# WIZ500SR_RP_EVB.net
KiCad netlist of a schematic drawn in Altium Designer
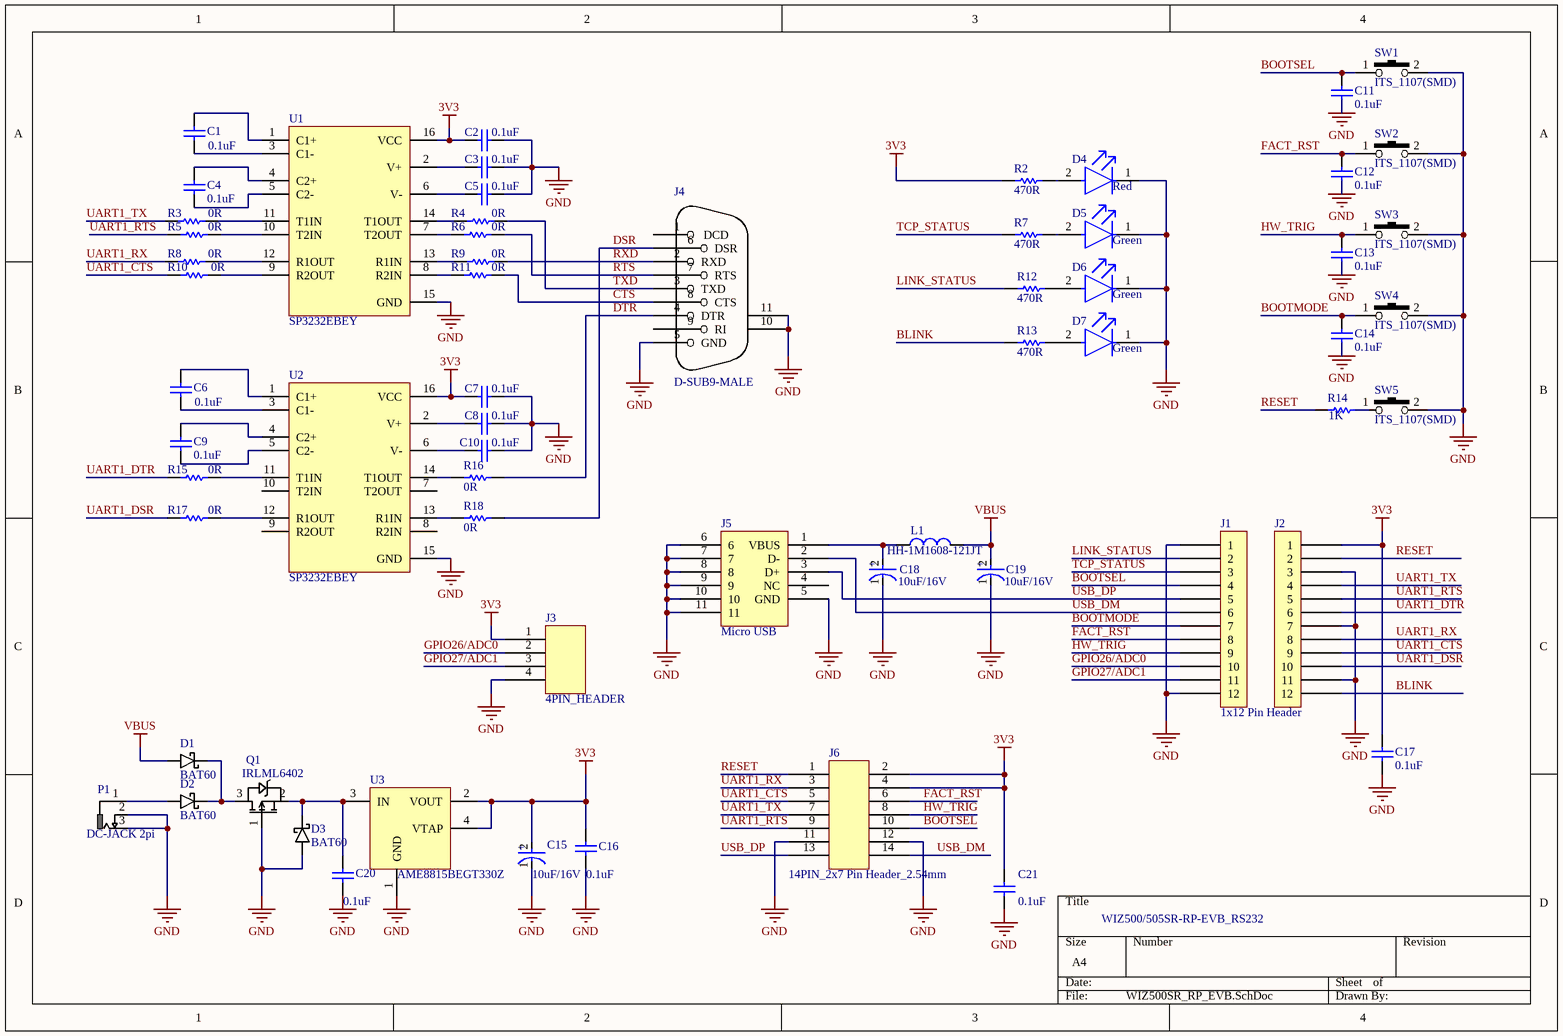
[diagram p0: WIZ500SR_RP_EVB.SchDoc]

(export (version "E")
  (design (tool "Eeschema 10.0.6"))
  (components
    (comp (ref "C1")
      (value "0.1uF")
      (footprint "CAPC1005X55X25ML5T10")
      (description "Chip Capacitor, 1 nF, +/- 10%, 50 V, -55 to 125 degC, 0402 (1005 Metric), RoHS, Tape and Reel")
      (fields (field (name "TOLERANCE") "10%"))
      (libsource (lib "Altium Content Vault") (part "CAP-NP-2"))
    )
    (comp (ref "C2")
      (value "0.1uF")
      (footprint "CAPC1005X55X25ML5T10")
      (description "Chip Capacitor, 1 nF, +/- 10%, 50 V, -55 to 125 degC, 0402 (1005 Metric), RoHS, Tape and Reel")
      (fields (field (name "TOLERANCE") "10%"))
      (libsource (lib "Altium Content Vault") (part "CAP-NP-2"))
    )
    (comp (ref "C3")
      (value "0.1uF")
      (footprint "CAPC1005X55X25ML5T10")
      (description "Chip Capacitor, 1 nF, +/- 10%, 50 V, -55 to 125 degC, 0402 (1005 Metric), RoHS, Tape and Reel")
      (fields (field (name "TOLERANCE") "10%"))
      (libsource (lib "Altium Content Vault") (part "CAP-NP-2"))
    )
    (comp (ref "C4")
      (value "0.1uF")
      (footprint "CAPC1005X55X25ML5T10")
      (description "Chip Capacitor, 1 nF, +/- 10%, 50 V, -55 to 125 degC, 0402 (1005 Metric), RoHS, Tape and Reel")
      (fields (field (name "TOLERANCE") "10%"))
      (libsource (lib "Altium Content Vault") (part "CAP-NP-2"))
    )
    (comp (ref "C5")
      (value "0.1uF")
      (footprint "CAPC1005X55X25ML5T10")
      (description "Chip Capacitor, 1 nF, +/- 10%, 50 V, -55 to 125 degC, 0402 (1005 Metric), RoHS, Tape and Reel")
      (fields (field (name "TOLERANCE") "10%"))
      (libsource (lib "Altium Content Vault") (part "CAP-NP-2"))
    )
    (comp (ref "C6")
      (value "0.1uF")
      (footprint "CAPC1005X55X25ML5T10")
      (description "Chip Capacitor, 1 nF, +/- 10%, 50 V, -55 to 125 degC, 0402 (1005 Metric), RoHS, Tape and Reel")
      (fields (field (name "TOLERANCE") "10%"))
      (libsource (lib "Altium Content Vault") (part "CAP-NP-2"))
    )
    (comp (ref "C7")
      (value "0.1uF")
      (footprint "CAPC1005X55X25ML5T10")
      (description "Chip Capacitor, 1 nF, +/- 10%, 50 V, -55 to 125 degC, 0402 (1005 Metric), RoHS, Tape and Reel")
      (fields (field (name "TOLERANCE") "10%"))
      (libsource (lib "Altium Content Vault") (part "CAP-NP-2"))
    )
    (comp (ref "C8")
      (value "0.1uF")
      (footprint "CAPC1005X55X25ML5T10")
      (description "Chip Capacitor, 1 nF, +/- 10%, 50 V, -55 to 125 degC, 0402 (1005 Metric), RoHS, Tape and Reel")
      (fields (field (name "TOLERANCE") "10%"))
      (libsource (lib "Altium Content Vault") (part "CAP-NP-2"))
    )
    (comp (ref "C9")
      (value "0.1uF")
      (footprint "CAPC1005X55X25ML5T10")
      (description "Chip Capacitor, 1 nF, +/- 10%, 50 V, -55 to 125 degC, 0402 (1005 Metric), RoHS, Tape and Reel")
      (fields (field (name "TOLERANCE") "10%"))
      (libsource (lib "Altium Content Vault") (part "CAP-NP-2"))
    )
    (comp (ref "C10")
      (value "0.1uF")
      (footprint "CAPC1005X55X25ML5T10")
      (description "Chip Capacitor, 1 nF, +/- 10%, 50 V, -55 to 125 degC, 0402 (1005 Metric), RoHS, Tape and Reel")
      (fields (field (name "TOLERANCE") "10%"))
      (libsource (lib "Altium Content Vault") (part "CAP-NP-2"))
    )
    (comp (ref "C11")
      (value "0.1uF")
      (footprint "CAPC1005X55X25ML5T10")
      (description "Chip Capacitor, 1 nF, +/- 10%, 50 V, -55 to 125 degC, 0402 (1005 Metric), RoHS, Tape and Reel")
      (fields (field (name "TOLERANCE") "10%"))
      (libsource (lib "Altium Content Vault") (part "CAP-NP-2"))
    )
    (comp (ref "C12")
      (value "0.1uF")
      (footprint "CAPC1005X55X25ML5T10")
      (description "Chip Capacitor, 1 nF, +/- 10%, 50 V, -55 to 125 degC, 0402 (1005 Metric), RoHS, Tape and Reel")
      (fields (field (name "TOLERANCE") "10%"))
      (libsource (lib "Altium Content Vault") (part "CAP-NP-2"))
    )
    (comp (ref "C13")
      (value "0.1uF")
      (footprint "CAPC1005X55X25ML5T10")
      (description "Chip Capacitor, 1 nF, +/- 10%, 50 V, -55 to 125 degC, 0402 (1005 Metric), RoHS, Tape and Reel")
      (fields (field (name "TOLERANCE") "10%"))
      (libsource (lib "Altium Content Vault") (part "CAP-NP-2"))
    )
    (comp (ref "C14")
      (value "0.1uF")
      (footprint "CAPC1005X55X25ML5T10")
      (description "Chip Capacitor, 1 nF, +/- 10%, 50 V, -55 to 125 degC, 0402 (1005 Metric), RoHS, Tape and Reel")
      (fields (field (name "TOLERANCE") "10%"))
      (libsource (lib "Altium Content Vault") (part "CAP-NP-2"))
    )
    (comp (ref "C15")
      (value "10uF/16V")
      (footprint "FP-T520A107M006ATE045-MFG")
      (description "CAP TANT POLY 100UF 6.3V 1206")
      (fields (field (name "TOLERANCE") "20%"))
      (libsource (lib "Altium Content Vault") (part "a00bbbee19879c290e62620ae7e47b1"))
    )
    (comp (ref "C16")
      (value "0.1uF")
      (footprint "CAPC1005X55X25ML5T10")
      (description "Chip Capacitor, 1 nF, +/- 10%, 50 V, -55 to 125 degC, 0402 (1005 Metric), RoHS, Tape and Reel")
      (fields (field (name "TOLERANCE") "10%"))
      (libsource (lib "Altium Content Vault") (part "CAP-NP-2"))
    )
    (comp (ref "C17")
      (value "0.1uF")
      (footprint "CAPC1005X55X25ML5T10")
      (description "Chip Capacitor, 1 nF, +/- 10%, 50 V, -55 to 125 degC, 0402 (1005 Metric), RoHS, Tape and Reel")
      (fields (field (name "TOLERANCE") "10%"))
      (libsource (lib "Altium Content Vault") (part "CAP-NP-2"))
    )
    (comp (ref "C18")
      (value "10uF/16V")
      (footprint "FP-T520A107M006ATE045-MFG")
      (description "CAP TANT POLY 100UF 6.3V 1206")
      (fields (field (name "TOLERANCE") "20%"))
      (libsource (lib "Altium Content Vault") (part "a00bbbee19879c290e62620ae7e47b1"))
    )
    (comp (ref "C19")
      (value "10uF/16V")
      (footprint "FP-T520A107M006ATE045-MFG")
      (description "CAP TANT POLY 100UF 6.3V 1206")
      (fields (field (name "TOLERANCE") "20%"))
      (libsource (lib "Altium Content Vault") (part "a00bbbee19879c290e62620ae7e47b1"))
    )
    (comp (ref "C20")
      (value "0.1uF")
      (footprint "CAPC1005X55X25ML5T10")
      (description "Chip Capacitor, 1 nF, +/- 10%, 50 V, -55 to 125 degC, 0402 (1005 Metric), RoHS, Tape and Reel")
      (fields (field (name "TOLERANCE") "10%"))
      (libsource (lib "Altium Content Vault") (part "CAP-NP-2"))
    )
    (comp (ref "C21")
      (value "0.1uF")
      (footprint "CAPC1005X55X25ML5T10")
      (description "Chip Capacitor, 1 nF, +/- 10%, 50 V, -55 to 125 degC, 0402 (1005 Metric), RoHS, Tape and Reel")
      (fields (field (name "TOLERANCE") "10%"))
      (libsource (lib "Altium Content Vault") (part "CAP-NP-2"))
    )
    (comp (ref "D1")
      (value "BAT60")
      (footprint "BAT60A")
      (libsource (lib "Integrated_Library1") (part "Schottky_Diode(BAT60)"))
    )
    (comp (ref "D2")
      (value "BAT60")
      (footprint "BAT60A")
      (libsource (lib "Integrated_Library1") (part "Schottky_Diode(BAT60)"))
    )
    (comp (ref "D3")
      (value "BAT60")
      (footprint "BAT60A")
      (libsource (lib "Integrated_Library1") (part "Schottky_Diode(BAT60)"))
    )
    (comp (ref "D4")
      (value "Red")
      (footprint "FP-LTST-C191TBKT-MFG")
      (description "LED BLUE CLEAR CHIP SMD")
      (libsource (lib "Altium Content Vault") (part "8706943c75ba83719d021d2fdc84c58"))
    )
    (comp (ref "D5")
      (value "Green")
      (footprint "FP-LTST-C191TBKT-MFG")
      (description "LED BLUE CLEAR CHIP SMD")
      (libsource (lib "Altium Content Vault") (part "8706943c75ba83719d021d2fdc84c58"))
    )
    (comp (ref "D6")
      (value "Green")
      (footprint "FP-LTST-C191TBKT-MFG")
      (description "LED BLUE CLEAR CHIP SMD")
      (libsource (lib "Altium Content Vault") (part "8706943c75ba83719d021d2fdc84c58"))
    )
    (comp (ref "D7")
      (value "Green")
      (footprint "FP-LTST-C191TBKT-MFG")
      (description "LED BLUE CLEAR CHIP SMD")
      (libsource (lib "Altium Content Vault") (part "8706943c75ba83719d021d2fdc84c58"))
    )
    (comp (ref "J1")
      (value "1x12 Pin Header")
      (footprint "12PIN_HEADER_2mm")
      (libsource (lib "Integrated_Library1") (part "12PIN_2mm"))
    )
    (comp (ref "J2")
      (value "1x12 Pin Header")
      (footprint "12PIN_HEADER_2mm")
      (libsource (lib "") (part "12PIN_2mm_1"))
    )
    (comp (ref "J3")
      (value "4PIN_HEADER")
      (footprint "4PIN_HEADER")
      (libsource (lib "Integrated_Library1") (part "4PIN"))
    )
    (comp (ref "J4")
      (value "D-SUB9-MALE")
      (footprint "D-SUB9-MALE")
      (libsource (lib "Integrated_Library1") (part "D-SUB9-MALE"))
    )
    (comp (ref "J5")
      (value "Micro USB")
      (footprint "USB-MICRO-B(SMD)")
      (libsource (lib "Integrated_Library1") (part "Micro USB 5Pin"))
    )
    (comp (ref "J6")
      (value "14PIN_2x7 Pin Header_2.54mm")
      (footprint "14PIN_HEADER_2x7")
      (libsource (lib "Integrated_Library1") (part "14PIN_2x7 Pin Header_2.54mm"))
    )
    (comp (ref "L1")
      (value "HH-1M1608-121JT")
      (footprint "HH-1M11608-121JT")
      (libsource (lib "Integrated_Library1") (part "HH-1M1608-121JT"))
    )
    (comp (ref "P1")
      (value "DC-JACK 2pi")
      (footprint "DC-JACK 2PI")
      (libsource (lib "Integrated_Library1") (part "DC-JACK 2pi"))
    )
    (comp (ref "Q1")
      (value "IRLML6402")
      (footprint "IRLML6402")
      (libsource (lib "Integrated_Library1") (part "IRLML6402"))
    )
    (comp (ref "R2")
      (value "470R")
      (footprint "RESC1005X40X25NL05T10")
      (fields (field (name "MANUFACTURER") "Yageo / Phycomp") (field (name "PART NUMBER") "RC0402JR-070RL"))
      (libsource (lib "Altium Content Vault") (part "RES"))
    )
    (comp (ref "R3")
      (value "0R")
      (footprint "RESC1005X40X25NL05T10")
      (fields (field (name "MANUFACTURER") "Yageo / Phycomp") (field (name "PART NUMBER") "RC0402JR-070RL"))
      (libsource (lib "Altium Content Vault") (part "RES"))
    )
    (comp (ref "R4")
      (value "0R")
      (footprint "RESC1005X40X25NL05T10")
      (fields (field (name "MANUFACTURER") "Yageo / Phycomp") (field (name "PART NUMBER") "RC0402JR-070RL"))
      (libsource (lib "Altium Content Vault") (part "RES"))
    )
    (comp (ref "R5")
      (value "0R")
      (footprint "RESC1005X40X25NL05T10")
      (fields (field (name "MANUFACTURER") "Yageo / Phycomp") (field (name "PART NUMBER") "RC0402JR-070RL"))
      (libsource (lib "Altium Content Vault") (part "RES"))
    )
    (comp (ref "R6")
      (value "0R")
      (footprint "RESC1005X40X25NL05T10")
      (fields (field (name "MANUFACTURER") "Yageo / Phycomp") (field (name "PART NUMBER") "RC0402JR-070RL"))
      (libsource (lib "Altium Content Vault") (part "RES"))
    )
    (comp (ref "R7")
      (value "470R")
      (footprint "RESC1005X40X25NL05T10")
      (fields (field (name "MANUFACTURER") "Yageo / Phycomp") (field (name "PART NUMBER") "RC0402JR-070RL"))
      (libsource (lib "Altium Content Vault") (part "RES"))
    )
    (comp (ref "R8")
      (value "0R")
      (footprint "RESC1005X40X25NL05T10")
      (fields (field (name "MANUFACTURER") "Yageo / Phycomp") (field (name "PART NUMBER") "RC0402JR-070RL"))
      (libsource (lib "Altium Content Vault") (part "RES"))
    )
    (comp (ref "R9")
      (value "0R")
      (footprint "RESC1005X40X25NL05T10")
      (fields (field (name "MANUFACTURER") "Yageo / Phycomp") (field (name "PART NUMBER") "RC0402JR-070RL"))
      (libsource (lib "Altium Content Vault") (part "RES"))
    )
    (comp (ref "R10")
      (value "0R")
      (footprint "RESC1005X40X25NL05T10")
      (fields (field (name "MANUFACTURER") "Yageo / Phycomp") (field (name "PART NUMBER") "RC0402JR-070RL"))
      (libsource (lib "Altium Content Vault") (part "RES"))
    )
    (comp (ref "R11")
      (value "0R")
      (footprint "RESC1005X40X25NL05T10")
      (fields (field (name "MANUFACTURER") "Yageo / Phycomp") (field (name "PART NUMBER") "RC0402JR-070RL"))
      (libsource (lib "Altium Content Vault") (part "RES"))
    )
    (comp (ref "R12")
      (value "470R")
      (footprint "RESC1005X40X25NL05T10")
      (fields (field (name "MANUFACTURER") "Yageo / Phycomp") (field (name "PART NUMBER") "RC0402JR-070RL"))
      (libsource (lib "Altium Content Vault") (part "RES"))
    )
    (comp (ref "R13")
      (value "470R")
      (footprint "RESC1005X40X25NL05T10")
      (fields (field (name "MANUFACTURER") "Yageo / Phycomp") (field (name "PART NUMBER") "RC0402JR-070RL"))
      (libsource (lib "Altium Content Vault") (part "RES"))
    )
    (comp (ref "R14")
      (value "1K")
      (footprint "RESC1005X40X25NL05T10")
      (fields (field (name "MANUFACTURER") "Yageo / Phycomp") (field (name "PART NUMBER") "RC0402JR-070RL"))
      (libsource (lib "Altium Content Vault") (part "RES"))
    )
    (comp (ref "R15")
      (value "0R")
      (footprint "RESC1005X40X25NL05T10")
      (fields (field (name "MANUFACTURER") "Yageo / Phycomp") (field (name "PART NUMBER") "RC0402JR-070RL"))
      (libsource (lib "Altium Content Vault") (part "RES"))
    )
    (comp (ref "R16")
      (value "0R")
      (footprint "RESC1005X40X25NL05T10")
      (fields (field (name "MANUFACTURER") "Yageo / Phycomp") (field (name "PART NUMBER") "RC0402JR-070RL"))
      (libsource (lib "Altium Content Vault") (part "RES"))
    )
    (comp (ref "R17")
      (value "0R")
      (footprint "RESC1005X40X25NL05T10")
      (fields (field (name "MANUFACTURER") "Yageo / Phycomp") (field (name "PART NUMBER") "RC0402JR-070RL"))
      (libsource (lib "Altium Content Vault") (part "RES"))
    )
    (comp (ref "R18")
      (value "0R")
      (footprint "RESC1005X40X25NL05T10")
      (fields (field (name "MANUFACTURER") "Yageo / Phycomp") (field (name "PART NUMBER") "RC0402JR-070RL"))
      (libsource (lib "Altium Content Vault") (part "RES"))
    )
    (comp (ref "SW1")
      (value "ITS_1107(SMD)")
      (footprint "IT-1107(SMD)")
      (libsource (lib "Integrated_Library1") (part "ITS_1107(SW)"))
    )
    (comp (ref "SW2")
      (value "ITS_1107(SMD)")
      (footprint "IT-1107(SMD)")
      (libsource (lib "Integrated_Library1") (part "ITS_1107(SW)"))
    )
    (comp (ref "SW3")
      (value "ITS_1107(SMD)")
      (footprint "IT-1107(SMD)")
      (libsource (lib "Integrated_Library1") (part "ITS_1107(SW)"))
    )
    (comp (ref "SW4")
      (value "ITS_1107(SMD)")
      (footprint "IT-1107(SMD)")
      (libsource (lib "Integrated_Library1") (part "ITS_1107(SW)"))
    )
    (comp (ref "SW5")
      (value "ITS_1107(SMD)")
      (footprint "IT-1107(SMD)")
      (libsource (lib "Integrated_Library1") (part "ITS_1107(SW)"))
    )
    (comp (ref "U1")
      (value "SP3232EBEY")
      (footprint "SP3232EBEY-TSSOP16")
      (libsource (lib "Integrated_Library1") (part "SP3232EBEY"))
    )
    (comp (ref "U2")
      (value "SP3232EBEY")
      (footprint "SP3232EBEY-TSSOP16")
      (libsource (lib "Integrated_Library1") (part "SP3232EBEY"))
    )
    (comp (ref "U3")
      (value "AME8815BEGT330Z")
      (footprint "AME8815BEGT330Z")
      (libsource (lib "Integrated_Library1") (part "AME8815BEGT330Z(3.3_LDO)"))
    )
  )
  (nets
    (net (code "2") (name "/BLINK") (class "Default")
      (node (ref "J2") (pin "12") (pinfunction "12_12") (pintype "passive"))
      (node (ref "R13") (pin "1") (pinfunction "1_1") (pintype "passive"))
    )
    (net (code "3") (name "/BOOTMODE") (class "Default")
      (node (ref "C14") (pin "2") (pinfunction "2_2") (pintype "passive"))
      (node (ref "J1") (pin "7") (pinfunction "7_7") (pintype "passive"))
      (node (ref "SW4") (pin "1") (pinfunction "1_1") (pintype "passive"))
    )
    (net (code "4") (name "/BOOTSEL") (class "Default")
      (node (ref "C11") (pin "2") (pinfunction "2_2") (pintype "passive"))
      (node (ref "J1") (pin "4") (pinfunction "4_4") (pintype "passive"))
      (node (ref "J6") (pin "10") (pintype "passive"))
      (node (ref "SW1") (pin "1") (pinfunction "1_1") (pintype "passive"))
    )
    (net (code "5") (name "/CTS") (class "Default")
      (node (ref "J4") (pin "8") (pinfunction "CTS_8") (pintype "passive"))
      (node (ref "R11") (pin "2") (pinfunction "2_2") (pintype "passive"))
    )
    (net (code "6") (name "/DSR") (class "Default")
      (node (ref "J4") (pin "6") (pinfunction "DSR_6") (pintype "passive"))
      (node (ref "R18") (pin "2") (pinfunction "2_2") (pintype "passive"))
    )
    (net (code "7") (name "/DTR") (class "Default")
      (node (ref "J4") (pin "4") (pinfunction "DTR_4") (pintype "passive"))
      (node (ref "R16") (pin "2") (pinfunction "2_2") (pintype "passive"))
    )
    (net (code "8") (name "/FACT_RST") (class "Default")
      (node (ref "C12") (pin "2") (pinfunction "2_2") (pintype "passive"))
      (node (ref "J1") (pin "8") (pinfunction "8_8") (pintype "passive"))
      (node (ref "J6") (pin "6") (pintype "passive"))
      (node (ref "SW2") (pin "1") (pinfunction "1_1") (pintype "passive"))
    )
    (net (code "9") (name "/GPIO26{slash}ADC0") (class "Default")
      (node (ref "J1") (pin "10") (pinfunction "10_10") (pintype "passive"))
      (node (ref "J3") (pin "2") (pintype "passive"))
    )
    (net (code "10") (name "/GPIO27{slash}ADC1") (class "Default")
      (node (ref "J1") (pin "11") (pinfunction "11_11") (pintype "passive"))
      (node (ref "J3") (pin "3") (pintype "passive"))
    )
    (net (code "11") (name "/HW_TRIG") (class "Default")
      (node (ref "C13") (pin "2") (pinfunction "2_2") (pintype "passive"))
      (node (ref "J1") (pin "9") (pinfunction "9_9") (pintype "passive"))
      (node (ref "J6") (pin "8") (pintype "passive"))
      (node (ref "SW3") (pin "1") (pinfunction "1_1") (pintype "passive"))
    )
    (net (code "12") (name "/LINK_STATUS") (class "Default")
      (node (ref "J1") (pin "2") (pinfunction "2_2") (pintype "passive"))
      (node (ref "R12") (pin "1") (pinfunction "1_1") (pintype "passive"))
    )
    (net (code "13") (name "/RESET") (class "Default")
      (node (ref "J2") (pin "2") (pinfunction "2_2") (pintype "passive"))
      (node (ref "J6") (pin "1") (pintype "passive"))
      (node (ref "R14") (pin "1") (pinfunction "1_1") (pintype "passive"))
    )
    (net (code "14") (name "/RTS") (class "Default")
      (node (ref "J4") (pin "7") (pinfunction "RTS_7") (pintype "passive"))
      (node (ref "R6") (pin "2") (pinfunction "2_2") (pintype "passive"))
    )
    (net (code "15") (name "/RXD") (class "Default")
      (node (ref "J4") (pin "2") (pinfunction "RXD_2") (pintype "passive"))
      (node (ref "R9") (pin "2") (pinfunction "2_2") (pintype "passive"))
    )
    (net (code "16") (name "/TCP_STATUS") (class "Default")
      (node (ref "J1") (pin "3") (pinfunction "3_3") (pintype "passive"))
      (node (ref "R7") (pin "1") (pinfunction "1_1") (pintype "passive"))
    )
    (net (code "17") (name "/TXD") (class "Default")
      (node (ref "J4") (pin "3") (pinfunction "TXD_3") (pintype "passive"))
      (node (ref "R4") (pin "2") (pinfunction "2_2") (pintype "passive"))
    )
    (net (code "18") (name "/UART1_CTS") (class "Default")
      (node (ref "J2") (pin "9") (pinfunction "9_9") (pintype "passive"))
      (node (ref "J6") (pin "5") (pintype "passive"))
      (node (ref "R10") (pin "1") (pinfunction "1_1") (pintype "passive"))
    )
    (net (code "19") (name "/UART1_DSR") (class "Default")
      (node (ref "J2") (pin "10") (pinfunction "10_10") (pintype "passive"))
      (node (ref "R17") (pin "1") (pinfunction "1_1") (pintype "passive"))
    )
    (net (code "20") (name "/UART1_DTR") (class "Default")
      (node (ref "J2") (pin "6") (pinfunction "6_6") (pintype "passive"))
      (node (ref "R15") (pin "1") (pinfunction "1_1") (pintype "passive"))
    )
    (net (code "21") (name "/UART1_RTS") (class "Default")
      (node (ref "J2") (pin "5") (pinfunction "5_5") (pintype "passive"))
      (node (ref "J6") (pin "9") (pintype "passive"))
      (node (ref "R5") (pin "1") (pinfunction "1_1") (pintype "passive"))
    )
    (net (code "22") (name "/UART1_RX") (class "Default")
      (node (ref "J2") (pin "8") (pinfunction "8_8") (pintype "passive"))
      (node (ref "J6") (pin "3") (pintype "passive"))
      (node (ref "R8") (pin "1") (pinfunction "1_1") (pintype "passive"))
    )
    (net (code "23") (name "/UART1_TX") (class "Default")
      (node (ref "J2") (pin "4") (pinfunction "4_4") (pintype "passive"))
      (node (ref "J6") (pin "7") (pintype "passive"))
      (node (ref "R3") (pin "1") (pinfunction "1_1") (pintype "passive"))
    )
    (net (code "24") (name "/USB_DM") (class "Default")
      (node (ref "J1") (pin "6") (pinfunction "6_6") (pintype "passive"))
      (node (ref "J5") (pin "2") (pinfunction "D-_2") (pintype "passive"))
      (node (ref "J6") (pin "14") (pintype "passive"))
    )
    (net (code "25") (name "/USB_DP") (class "Default")
      (node (ref "J1") (pin "5") (pinfunction "5_5") (pintype "passive"))
      (node (ref "J5") (pin "3") (pinfunction "D+_3") (pintype "passive"))
      (node (ref "J6") (pin "13") (pintype "passive"))
    )
    (net (code "26") (name "3V3") (class "Default")
      (node (ref "C15") (pin "2") (pinfunction "A_2") (pintype "passive"))
      (node (ref "C16") (pin "2") (pinfunction "2_2") (pintype "passive"))
      (node (ref "C17") (pin "2") (pinfunction "2_2") (pintype "passive"))
      (node (ref "C2") (pin "1") (pinfunction "1_1") (pintype "passive"))
      (node (ref "C21") (pin "2") (pinfunction "2_2") (pintype "passive"))
      (node (ref "C7") (pin "1") (pinfunction "1_1") (pintype "passive"))
      (node (ref "J2") (pin "1") (pinfunction "1_1") (pintype "passive"))
      (node (ref "J3") (pin "1") (pintype "passive"))
      (node (ref "J6") (pin "2") (pintype "passive"))
      (node (ref "J6") (pin "4") (pintype "passive"))
      (node (ref "R2") (pin "1") (pinfunction "1_1") (pintype "passive"))
      (node (ref "U1") (pin "16") (pinfunction "VCC_16") (pintype "passive"))
      (node (ref "U2") (pin "16") (pinfunction "VCC_16") (pintype "passive"))
      (node (ref "U3") (pin "2") (pinfunction "VOUT_2") (pintype "passive"))
      (node (ref "U3") (pin "4") (pinfunction "VTAP_4") (pintype "passive"))
    )
    (net (code "27") (name "GND") (class "Default")
      (node (ref "C10") (pin "2") (pinfunction "2_2") (pintype "passive"))
      (node (ref "C11") (pin "1") (pinfunction "1_1") (pintype "passive"))
      (node (ref "C12") (pin "1") (pinfunction "1_1") (pintype "passive"))
      (node (ref "C13") (pin "1") (pinfunction "1_1") (pintype "passive"))
      (node (ref "C14") (pin "1") (pinfunction "1_1") (pintype "passive"))
      (node (ref "C15") (pin "1") (pinfunction "C_1") (pintype "passive"))
      (node (ref "C16") (pin "1") (pinfunction "1_1") (pintype "passive"))
      (node (ref "C17") (pin "1") (pinfunction "1_1") (pintype "passive"))
      (node (ref "C18") (pin "1") (pinfunction "C_1") (pintype "passive"))
      (node (ref "C19") (pin "1") (pinfunction "C_1") (pintype "passive"))
      (node (ref "C2") (pin "2") (pinfunction "2_2") (pintype "passive"))
      (node (ref "C20") (pin "1") (pinfunction "1_1") (pintype "passive"))
      (node (ref "C21") (pin "1") (pinfunction "1_1") (pintype "passive"))
      (node (ref "C3") (pin "2") (pinfunction "2_2") (pintype "passive"))
      (node (ref "C5") (pin "2") (pinfunction "2_2") (pintype "passive"))
      (node (ref "C7") (pin "2") (pinfunction "2_2") (pintype "passive"))
      (node (ref "C8") (pin "2") (pinfunction "2_2") (pintype "passive"))
      (node (ref "D3") (pin "2") (pinfunction "2_2") (pintype "passive"))
      (node (ref "D4") (pin "1") (pinfunction "C_1") (pintype "passive"))
      (node (ref "D5") (pin "1") (pinfunction "C_1") (pintype "passive"))
      (node (ref "D6") (pin "1") (pinfunction "C_1") (pintype "passive"))
      (node (ref "D7") (pin "1") (pinfunction "C_1") (pintype "passive"))
      (node (ref "J1") (pin "1") (pinfunction "1_1") (pintype "passive"))
      (node (ref "J1") (pin "12") (pinfunction "12_12") (pintype "passive"))
      (node (ref "J2") (pin "11") (pinfunction "11_11") (pintype "passive"))
      (node (ref "J2") (pin "3") (pinfunction "3_3") (pintype "passive"))
      (node (ref "J2") (pin "7") (pinfunction "7_7") (pintype "passive"))
      (node (ref "J3") (pin "4") (pintype "passive"))
      (node (ref "J4") (pin "10") (pintype "passive"))
      (node (ref "J4") (pin "11") (pintype "passive"))
      (node (ref "J4") (pin "5") (pinfunction "GND_5") (pintype "passive"))
      (node (ref "J5") (pin "10") (pinfunction "10_10") (pintype "passive"))
      (node (ref "J5") (pin "11") (pinfunction "11_11") (pintype "passive"))
      (node (ref "J5") (pin "5") (pinfunction "GND_5") (pintype "passive"))
      (node (ref "J5") (pin "6") (pinfunction "6_6") (pintype "passive"))
      (node (ref "J5") (pin "7") (pinfunction "7_7") (pintype "passive"))
      (node (ref "J5") (pin "8") (pinfunction "8_8") (pintype "passive"))
      (node (ref "J5") (pin "9") (pinfunction "9_9") (pintype "passive"))
      (node (ref "J6") (pin "11") (pintype "passive"))
      (node (ref "J6") (pin "12") (pintype "passive"))
      (node (ref "P1") (pin "2") (pinfunction "24_2") (pintype "passive"))
      (node (ref "P1") (pin "3") (pinfunction "3_3") (pintype "passive"))
      (node (ref "Q1") (pin "1") (pinfunction "1_1") (pintype "passive"))
      (node (ref "SW1") (pin "2") (pinfunction "2_2") (pintype "passive"))
      (node (ref "SW2") (pin "2") (pinfunction "2_2") (pintype "passive"))
      (node (ref "SW3") (pin "2") (pinfunction "2_2") (pintype "passive"))
      (node (ref "SW4") (pin "2") (pinfunction "2_2") (pintype "passive"))
      (node (ref "SW5") (pin "2") (pinfunction "2_2") (pintype "passive"))
      (node (ref "U1") (pin "15") (pinfunction "GND_15") (pintype "passive"))
      (node (ref "U2") (pin "15") (pinfunction "GND_15") (pintype "passive"))
      (node (ref "U3") (pin "1") (pinfunction "GND_1") (pintype "passive"))
    )
    (net (code "28") (name "Net-(C18-A)") (class "Default")
      (node (ref "C18") (pin "2") (pinfunction "A_2") (pintype "passive"))
      (node (ref "J5") (pin "1") (pinfunction "VBUS_1") (pintype "passive"))
      (node (ref "L1") (pin "1") (pinfunction "1_1") (pintype "passive"))
    )
    (net (code "29") (name "Net-(D1-Pad1)") (class "Default")
      (node (ref "D1") (pin "1") (pinfunction "1_1") (pintype "passive"))
      (node (ref "D2") (pin "1") (pinfunction "1_1") (pintype "passive"))
      (node (ref "Q1") (pin "3") (pinfunction "3_3") (pintype "passive"))
    )
    (net (code "30") (name "Net-(D2-Pad2)") (class "Default")
      (node (ref "D2") (pin "2") (pinfunction "2_2") (pintype "passive"))
      (node (ref "P1") (pin "1") (pinfunction "1_1") (pintype "passive"))
    )
    (net (code "31") (name "Net-(D4-A)") (class "Default")
      (node (ref "D4") (pin "2") (pinfunction "A_2") (pintype "passive"))
      (node (ref "R2") (pin "2") (pinfunction "2_2") (pintype "passive"))
    )
    (net (code "32") (name "Net-(D5-A)") (class "Default")
      (node (ref "D5") (pin "2") (pinfunction "A_2") (pintype "passive"))
      (node (ref "R7") (pin "2") (pinfunction "2_2") (pintype "passive"))
    )
    (net (code "33") (name "Net-(D6-A)") (class "Default")
      (node (ref "D6") (pin "2") (pinfunction "A_2") (pintype "passive"))
      (node (ref "R12") (pin "2") (pinfunction "2_2") (pintype "passive"))
    )
    (net (code "34") (name "Net-(D7-A)") (class "Default")
      (node (ref "D7") (pin "2") (pinfunction "A_2") (pintype "passive"))
      (node (ref "R13") (pin "2") (pinfunction "2_2") (pintype "passive"))
    )
    (net (code "35") (name "Net-(R14-Pad2)") (class "Default")
      (node (ref "R14") (pin "2") (pinfunction "2_2") (pintype "passive"))
      (node (ref "SW5") (pin "1") (pinfunction "1_1") (pintype "passive"))
    )
    (net (code "36") (name "Net-(U1-C1+)") (class "Default")
      (node (ref "C1") (pin "2") (pinfunction "2_2") (pintype "passive"))
      (node (ref "U1") (pin "1") (pinfunction "C1+_1") (pintype "passive"))
    )
    (net (code "37") (name "Net-(U1-C1-)") (class "Default")
      (node (ref "C1") (pin "1") (pinfunction "1_1") (pintype "passive"))
      (node (ref "U1") (pin "3") (pinfunction "C1-_3") (pintype "passive"))
    )
    (net (code "38") (name "Net-(U1-C2+)") (class "Default")
      (node (ref "C4") (pin "2") (pinfunction "2_2") (pintype "passive"))
      (node (ref "U1") (pin "4") (pinfunction "C2+_4") (pintype "passive"))
    )
    (net (code "39") (name "Net-(U1-C2-)") (class "Default")
      (node (ref "C4") (pin "1") (pinfunction "1_1") (pintype "passive"))
      (node (ref "U1") (pin "5") (pinfunction "C2-_5") (pintype "passive"))
    )
    (net (code "40") (name "Net-(U1-R1IN)") (class "Default")
      (node (ref "R9") (pin "1") (pinfunction "1_1") (pintype "passive"))
      (node (ref "U1") (pin "13") (pinfunction "R1IN_13") (pintype "passive"))
    )
    (net (code "41") (name "Net-(U1-R1OUT)") (class "Default")
      (node (ref "R8") (pin "2") (pinfunction "2_2") (pintype "passive"))
      (node (ref "U1") (pin "12") (pinfunction "R1OUT_12") (pintype "passive"))
    )
    (net (code "42") (name "Net-(U1-R2IN)") (class "Default")
      (node (ref "R11") (pin "1") (pinfunction "1_1") (pintype "passive"))
      (node (ref "U1") (pin "8") (pinfunction "R2IN_8") (pintype "passive"))
    )
    (net (code "43") (name "Net-(U1-R2OUT)") (class "Default")
      (node (ref "R10") (pin "2") (pinfunction "2_2") (pintype "passive"))
      (node (ref "U1") (pin "9") (pinfunction "R2OUT_9") (pintype "passive"))
    )
    (net (code "44") (name "Net-(U1-T1IN)") (class "Default")
      (node (ref "R3") (pin "2") (pinfunction "2_2") (pintype "passive"))
      (node (ref "U1") (pin "11") (pinfunction "T1IN_11") (pintype "passive"))
    )
    (net (code "45") (name "Net-(U1-T1OUT)") (class "Default")
      (node (ref "R4") (pin "1") (pinfunction "1_1") (pintype "passive"))
      (node (ref "U1") (pin "14") (pinfunction "T1OUT_14") (pintype "passive"))
    )
    (net (code "46") (name "Net-(U1-T2IN)") (class "Default")
      (node (ref "R5") (pin "2") (pinfunction "2_2") (pintype "passive"))
      (node (ref "U1") (pin "10") (pinfunction "T2IN_10") (pintype "passive"))
    )
    (net (code "47") (name "Net-(U1-T2OUT)") (class "Default")
      (node (ref "R6") (pin "1") (pinfunction "1_1") (pintype "passive"))
      (node (ref "U1") (pin "7") (pinfunction "T2OUT_7") (pintype "passive"))
    )
    (net (code "48") (name "Net-(U1-V+)") (class "Default")
      (node (ref "C3") (pin "1") (pinfunction "1_1") (pintype "passive"))
      (node (ref "U1") (pin "2") (pinfunction "V+_2") (pintype "passive"))
    )
    (net (code "49") (name "Net-(U1-V-)") (class "Default")
      (node (ref "C5") (pin "1") (pinfunction "1_1") (pintype "passive"))
      (node (ref "U1") (pin "6") (pinfunction "V-_6") (pintype "passive"))
    )
    (net (code "50") (name "Net-(U2-C1+)") (class "Default")
      (node (ref "C6") (pin "2") (pinfunction "2_2") (pintype "passive"))
      (node (ref "U2") (pin "1") (pinfunction "C1+_1") (pintype "passive"))
    )
    (net (code "51") (name "Net-(U2-C1-)") (class "Default")
      (node (ref "C6") (pin "1") (pinfunction "1_1") (pintype "passive"))
      (node (ref "U2") (pin "3") (pinfunction "C1-_3") (pintype "passive"))
    )
    (net (code "52") (name "Net-(U2-C2+)") (class "Default")
      (node (ref "C9") (pin "2") (pinfunction "2_2") (pintype "passive"))
      (node (ref "U2") (pin "4") (pinfunction "C2+_4") (pintype "passive"))
    )
    (net (code "53") (name "Net-(U2-C2-)") (class "Default")
      (node (ref "C9") (pin "1") (pinfunction "1_1") (pintype "passive"))
      (node (ref "U2") (pin "5") (pinfunction "C2-_5") (pintype "passive"))
    )
    (net (code "54") (name "Net-(U2-R1IN)") (class "Default")
      (node (ref "R18") (pin "1") (pinfunction "1_1") (pintype "passive"))
      (node (ref "U2") (pin "13") (pinfunction "R1IN_13") (pintype "passive"))
    )
    (net (code "55") (name "Net-(U2-R1OUT)") (class "Default")
      (node (ref "R17") (pin "2") (pinfunction "2_2") (pintype "passive"))
      (node (ref "U2") (pin "12") (pinfunction "R1OUT_12") (pintype "passive"))
    )
    (net (code "56") (name "Net-(U2-T1IN)") (class "Default")
      (node (ref "R15") (pin "2") (pinfunction "2_2") (pintype "passive"))
      (node (ref "U2") (pin "11") (pinfunction "T1IN_11") (pintype "passive"))
    )
    (net (code "57") (name "Net-(U2-T1OUT)") (class "Default")
      (node (ref "R16") (pin "1") (pinfunction "1_1") (pintype "passive"))
      (node (ref "U2") (pin "14") (pinfunction "T1OUT_14") (pintype "passive"))
    )
    (net (code "58") (name "Net-(U2-V+)") (class "Default")
      (node (ref "C8") (pin "1") (pinfunction "1_1") (pintype "passive"))
      (node (ref "U2") (pin "2") (pinfunction "V+_2") (pintype "passive"))
    )
    (net (code "59") (name "Net-(U2-V-)") (class "Default")
      (node (ref "C10") (pin "1") (pinfunction "1_1") (pintype "passive"))
      (node (ref "U2") (pin "6") (pinfunction "V-_6") (pintype "passive"))
    )
    (net (code "60") (name "Net-(U3-IN)") (class "Default")
      (node (ref "C20") (pin "2") (pinfunction "2_2") (pintype "passive"))
      (node (ref "D3") (pin "1") (pinfunction "1_1") (pintype "passive"))
      (node (ref "Q1") (pin "2") (pinfunction "2_2") (pintype "passive"))
      (node (ref "U3") (pin "3") (pinfunction "IN_3") (pintype "passive"))
    )
    (net (code "61") (name "VBUS") (class "Default")
      (node (ref "C19") (pin "2") (pinfunction "A_2") (pintype "passive"))
      (node (ref "D1") (pin "2") (pinfunction "2_2") (pintype "passive"))
      (node (ref "L1") (pin "2") (pinfunction "2_2") (pintype "passive"))
    )
    (net (code "62") (name "unconnected-(J4-DCD-Pad1)") (class "Default")
      (node (ref "J4") (pin "1") (pinfunction "DCD_1") (pintype "passive"))
    )
    (net (code "63") (name "unconnected-(J4-RI-Pad9)") (class "Default")
      (node (ref "J4") (pin "9") (pinfunction "RI_9") (pintype "passive"))
    )
    (net (code "64") (name "unconnected-(J5-NC-Pad4)") (class "Default")
      (node (ref "J5") (pin "4") (pinfunction "NC_4") (pintype "passive"))
    )
    (net (code "65") (name "unconnected-(U2-R2IN-Pad8)") (class "Default")
      (node (ref "U2") (pin "8") (pinfunction "R2IN_8") (pintype "passive"))
    )
    (net (code "66") (name "unconnected-(U2-R2OUT-Pad9)") (class "Default")
      (node (ref "U2") (pin "9") (pinfunction "R2OUT_9") (pintype "passive"))
    )
    (net (code "67") (name "unconnected-(U2-T2IN-Pad10)") (class "Default")
      (node (ref "U2") (pin "10") (pinfunction "T2IN_10") (pintype "passive"))
    )
    (net (code "68") (name "unconnected-(U2-T2OUT-Pad7)") (class "Default")
      (node (ref "U2") (pin "7") (pinfunction "T2OUT_7") (pintype "passive"))
    )
  )
)
